# design.net
KiCad netlist of a schematic drawn in Altium Designer
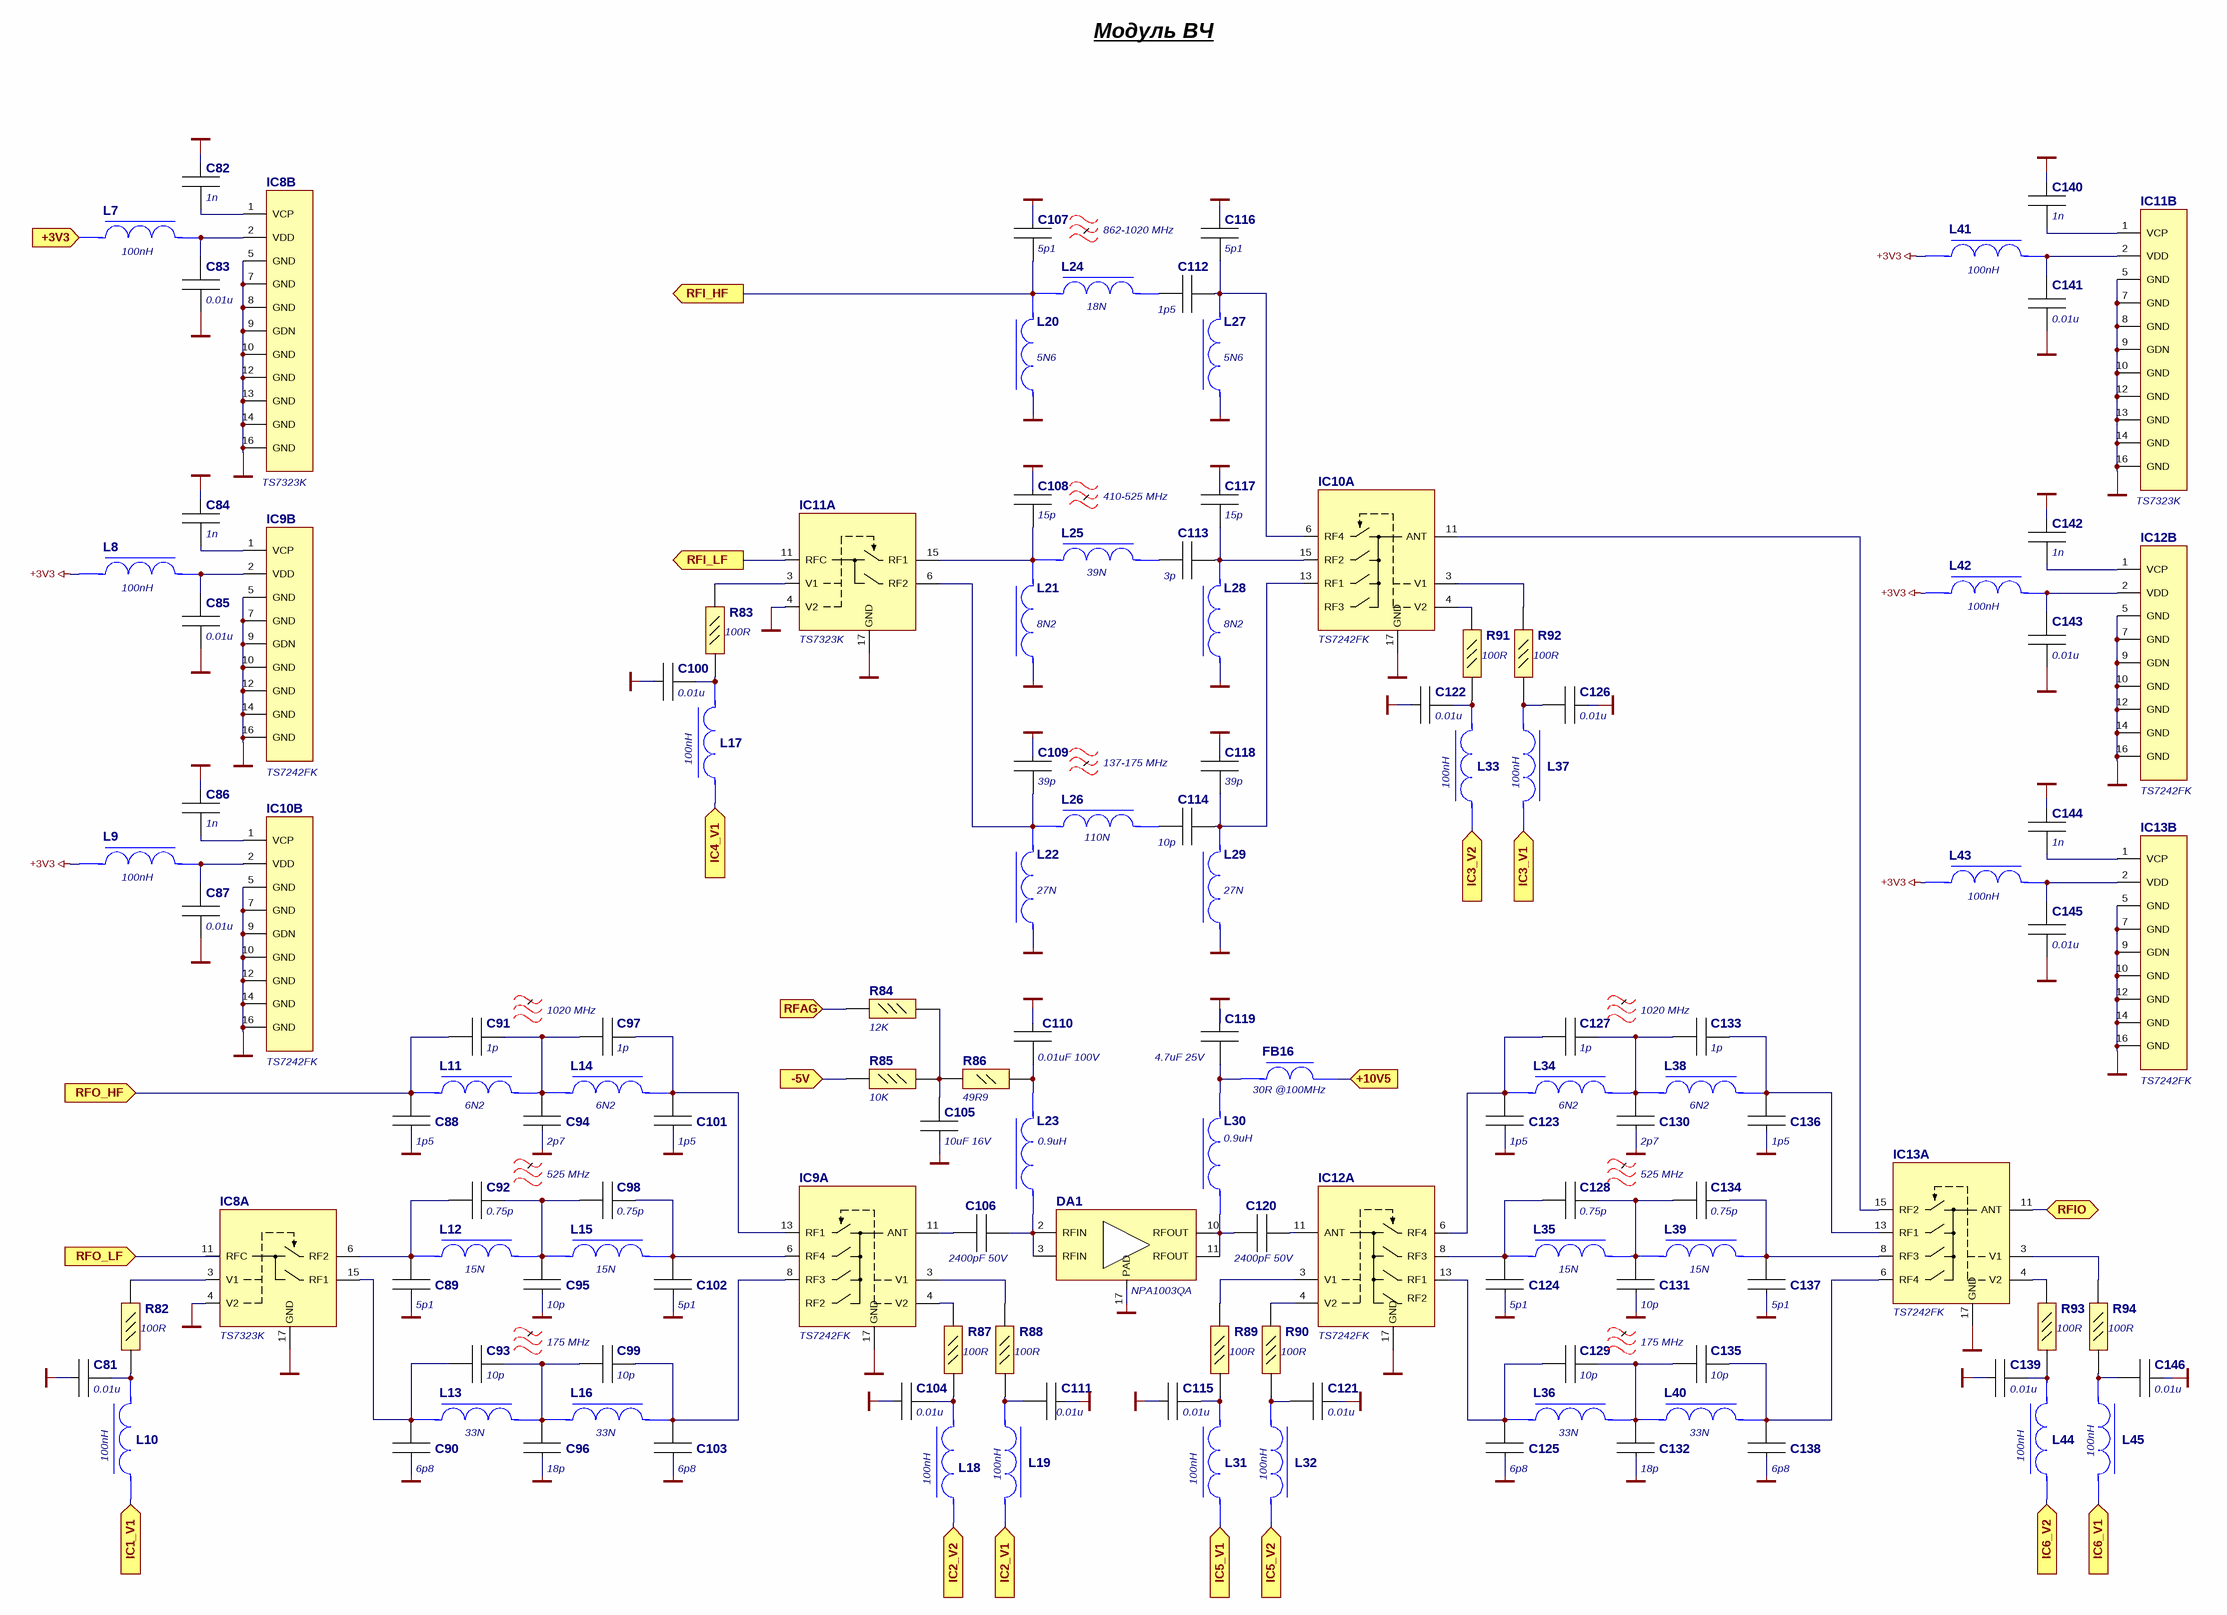
[diagram p0: Модуль ВЧ.SchDoc]

(export (version "E")
  (design (tool "Eeschema 10.0.6"))
  (components
    (comp (ref "C81")
      (value "0.01u")
      (footprint ":CAP0402 100x50x50")
      (description "±5% 35V Ceramic Capacitor C0G, NP0 0402 (1005 Metric)")
      (fields (field (name "MANUFACTURER_PART_NUMBER") "GRM1555CYA103JE01D"))
      (libsource (lib "Capacitors 0402") (part "GRM1555CYA103JE01D"))
    )
    (comp (ref "C82")
      (value "1n")
      (footprint ":CAP0402 100x50x50")
      (description "±5% 50V Ceramic Capacitor C0G, NP0 0402 (1005 Metric)")
      (fields (field (name "MANUFACTURER_PART_NUMBER") "GRM1555C1H102JA01J"))
      (libsource (lib "Capacitors 0402") (part "GRM1555C1H102JA01J"))
    )
    (comp (ref "C83")
      (value "0.01u")
      (footprint ":CAP0402 100x50x50")
      (description "±5% 35V Ceramic Capacitor C0G, NP0 0402 (1005 Metric)")
      (fields (field (name "MANUFACTURER_PART_NUMBER") "GRM1555CYA103JE01D"))
      (libsource (lib "Capacitors 0402") (part "GRM1555CYA103JE01D"))
    )
    (comp (ref "C84")
      (value "1n")
      (footprint ":CAP0402 100x50x50")
      (description "±5% 50V Ceramic Capacitor C0G, NP0 0402 (1005 Metric)")
      (fields (field (name "MANUFACTURER_PART_NUMBER") "GRM1555C1H102JA01J"))
      (libsource (lib "Capacitors 0402") (part "GRM1555C1H102JA01J"))
    )
    (comp (ref "C85")
      (value "0.01u")
      (footprint ":CAP0402 100x50x50")
      (description "±5% 35V Ceramic Capacitor C0G, NP0 0402 (1005 Metric)")
      (fields (field (name "MANUFACTURER_PART_NUMBER") "GRM1555CYA103JE01D"))
      (libsource (lib "Capacitors 0402") (part "GRM1555CYA103JE01D"))
    )
    (comp (ref "C86")
      (value "1n")
      (footprint ":CAP0402 100x50x50")
      (description "±5% 50V Ceramic Capacitor C0G, NP0 0402 (1005 Metric)")
      (fields (field (name "MANUFACTURER_PART_NUMBER") "GRM1555C1H102JA01J"))
      (libsource (lib "Capacitors 0402") (part "GRM1555C1H102JA01J"))
    )
    (comp (ref "C87")
      (value "0.01u")
      (footprint ":CAP0402 100x50x50")
      (description "±5% 35V Ceramic Capacitor C0G, NP0 0402 (1005 Metric)")
      (fields (field (name "MANUFACTURER_PART_NUMBER") "GRM1555CYA103JE01D"))
      (libsource (lib "Capacitors 0402") (part "GRM1555CYA103JE01D"))
    )
    (comp (ref "C88")
      (value "1p5")
      (footprint ":CAP0603 C1608х08")
      (description "Ceramic Capacitor ±0.1pF 250V C0G, NP0 0603 (1608 Metric)")
      (fields (field (name "MANUFACTURER_PART_NUMBER") "GQM1875C2E1R5BB12D"))
      (libsource (lib "Capacitors 0603 ±0.1pF 250V NP0") (part "GQM1875C2E1R5BB12D"))
    )
    (comp (ref "C89")
      (value "5p1")
      (footprint ":CAP0603 C1608х08")
      (description "Ceramic Capacitor ±0.1pF 250V C0G, NP0 0603 (1608 Metric)")
      (fields (field (name "MANUFACTURER_PART_NUMBER") "GQM1875C2E5R1BB12D"))
      (libsource (lib "Capacitors 0603 ±0.1pF 250V NP0") (part "GQM1875C2E5R1BB12D"))
    )
    (comp (ref "C90")
      (value "6p8")
      (footprint ":CAP0603 C1608х08")
      (description "Ceramic Capacitor ±0.1pF 250V C0G, NP0 0603 (1608 Metric)")
      (fields (field (name "MANUFACTURER_PART_NUMBER") "GQM1875C2E6R8BB12D"))
      (libsource (lib "Capacitors 0603 ±0.1pF 250V NP0") (part "GQM1875C2E6R8BB12D"))
    )
    (comp (ref "C91")
      (value "1p")
      (footprint ":CAP0603 C1608х08")
      (description "Ceramic Capacitor ±0.1pF 250V C0G, NP0 0603 (1608 Metric)")
      (fields (field (name "MANUFACTURER_PART_NUMBER") "GQM1875C2E1R0BB12D"))
      (libsource (lib "Capacitors 0603 ±0.1pF 250V NP0") (part "GQM1875C2E1R0BB12D"))
    )
    (comp (ref "C92")
      (value "0.75p")
      (footprint ":CAP0603 C1608х08")
      (description "Ceramic Capacitor ±0.1pF 250V C0G, NP0 0603 (1608 Metric)")
      (fields (field (name "MANUFACTURER_PART_NUMBER") "GQM1875C2ER75BB12D"))
      (libsource (lib "Capacitors 0603 ±0.1pF 250V NP0") (part "GQM1875C2ER75BB12D"))
    )
    (comp (ref "C93")
      (value "10p")
      (footprint ":CAP0603 C1608х08")
      (description "Ceramic Capacitor ±1% 250V C0G, NP0 0603 (1608 Metric)")
      (fields (field (name "MANUFACTURER_PART_NUMBER") "GQM1875C2E100FB12D"))
      (libsource (lib "Capacitors 0603 1% 250V NP0") (part "GQM1875C2E100FB12D"))
    )
    (comp (ref "C94")
      (value "2p7")
      (footprint ":CAP0603 C1608х08")
      (description "Ceramic Capacitor ±0.1pF 250V C0G, NP0 0603 (1608 Metric)")
      (fields (field (name "MANUFACTURER_PART_NUMBER") "GQM1875C2E2R7BB12D"))
      (libsource (lib "Capacitors 0603 ±0.1pF 250V NP0") (part "GQM1875C2E2R7BB12D"))
    )
    (comp (ref "C95")
      (value "10p")
      (footprint ":CAP0603 C1608х08")
      (description "Ceramic Capacitor ±1% 250V C0G, NP0 0603 (1608 Metric)")
      (fields (field (name "MANUFACTURER_PART_NUMBER") "GQM1875C2E100FB12D"))
      (libsource (lib "Capacitors 0603 1% 250V NP0") (part "GQM1875C2E100FB12D"))
    )
    (comp (ref "C96")
      (value "18p")
      (footprint ":CAP0603 C1608х08")
      (description "Ceramic Capacitor ±1% 250V C0G, NP0 0603 (1608 Metric)")
      (fields (field (name "MANUFACTURER_PART_NUMBER") "GQM1875C2E180FB12D"))
      (libsource (lib "Capacitors 0603 1% 250V NP0") (part "GQM1875C2E180FB12D"))
    )
    (comp (ref "C97")
      (value "1p")
      (footprint ":CAP0603 C1608х08")
      (description "Ceramic Capacitor ±0.1pF 250V C0G, NP0 0603 (1608 Metric)")
      (fields (field (name "MANUFACTURER_PART_NUMBER") "GQM1875C2E1R0BB12D"))
      (libsource (lib "Capacitors 0603 ±0.1pF 250V NP0") (part "GQM1875C2E1R0BB12D"))
    )
    (comp (ref "C98")
      (value "0.75p")
      (footprint ":CAP0603 C1608х08")
      (description "Ceramic Capacitor ±0.1pF 250V C0G, NP0 0603 (1608 Metric)")
      (fields (field (name "MANUFACTURER_PART_NUMBER") "GQM1875C2ER75BB12D"))
      (libsource (lib "Capacitors 0603 ±0.1pF 250V NP0") (part "GQM1875C2ER75BB12D"))
    )
    (comp (ref "C99")
      (value "10p")
      (footprint ":CAP0603 C1608х08")
      (description "Ceramic Capacitor ±1% 250V C0G, NP0 0603 (1608 Metric)")
      (fields (field (name "MANUFACTURER_PART_NUMBER") "GQM1875C2E100FB12D"))
      (libsource (lib "Capacitors 0603 1% 250V NP0") (part "GQM1875C2E100FB12D"))
    )
    (comp (ref "C100")
      (value "0.01u")
      (footprint ":CAP0402 100x50x50")
      (description "±5% 35V Ceramic Capacitor C0G, NP0 0402 (1005 Metric)")
      (fields (field (name "MANUFACTURER_PART_NUMBER") "GRM1555CYA103JE01D"))
      (libsource (lib "Capacitors 0402") (part "GRM1555CYA103JE01D"))
    )
    (comp (ref "C101")
      (value "1p5")
      (footprint ":CAP0603 C1608х08")
      (description "Ceramic Capacitor ±0.1pF 250V C0G, NP0 0603 (1608 Metric)")
      (fields (field (name "MANUFACTURER_PART_NUMBER") "GQM1875C2E1R5BB12D"))
      (libsource (lib "Capacitors 0603 ±0.1pF 250V NP0") (part "GQM1875C2E1R5BB12D"))
    )
    (comp (ref "C102")
      (value "5p1")
      (footprint ":CAP0603 C1608х08")
      (description "Ceramic Capacitor ±0.1pF 250V C0G, NP0 0603 (1608 Metric)")
      (fields (field (name "MANUFACTURER_PART_NUMBER") "GQM1875C2E5R1BB12D"))
      (libsource (lib "Capacitors 0603 ±0.1pF 250V NP0") (part "GQM1875C2E5R1BB12D"))
    )
    (comp (ref "C103")
      (value "6p8")
      (footprint ":CAP0603 C1608х08")
      (description "Ceramic Capacitor ±0.1pF 250V C0G, NP0 0603 (1608 Metric)")
      (fields (field (name "MANUFACTURER_PART_NUMBER") "GQM1875C2E6R8BB12D"))
      (libsource (lib "Capacitors 0603 ±0.1pF 250V NP0") (part "GQM1875C2E6R8BB12D"))
    )
    (comp (ref "C104")
      (value "0.01u")
      (footprint ":CAP0402 100x50x50")
      (description "±5% 35V Ceramic Capacitor C0G, NP0 0402 (1005 Metric)")
      (fields (field (name "MANUFACTURER_PART_NUMBER") "GRM1555CYA103JE01D"))
      (libsource (lib "Capacitors 0402") (part "GRM1555CYA103JE01D"))
    )
    (comp (ref "C105")
      (value "10uF 16V")
      (footprint ":CAP0805 C2012X125")
      (description "CAP CER 10uF 16V X5R 0805")
      (fields
        (field (name "MANUFACTURER_PART_NUMBER") "C2012X5R1C106M085AC")
        (field (name "MOUSER PART NUMBER") "810-C2012X5R1C106M-2")
      )
      (libsource (lib "Capacitors 0805") (part "C2012X5R1C106M085AC"))
    )
    (comp (ref "C106")
      (value "2400pF 50V")
      (footprint ":CAP0805 C2012X125")
      (description "2400pF 50V Ceramic Capacitor 0805 (2012 Metric)")
      (fields (field (name "MANUFACTURER_PART_NUMBER") "C08BL242X-5UN-X0T"))
      (libsource (lib "Capacitors 0805") (part "C08BL242X-5UN-X0T"))
    )
    (comp (ref "C107")
      (value "5p1")
      (footprint ":CAP0603 C1608х08")
      (description "Ceramic Capacitor ±0.1pF 250V C0G, NP0 0603 (1608 Metric)")
      (fields (field (name "MANUFACTURER_PART_NUMBER") "GQM1875C2E5R1BB12D"))
      (libsource (lib "Capacitors 0603 ±0.1pF 250V NP0") (part "GQM1875C2E5R1BB12D"))
    )
    (comp (ref "C108")
      (value "15p")
      (footprint ":CAP0603 C1608х08")
      (description "Ceramic Capacitor ±1% 250V C0G, NP0 0603 (1608 Metric)")
      (fields (field (name "MANUFACTURER_PART_NUMBER") "GQM1875C2E150FB12D"))
      (libsource (lib "Capacitors 0603 1% 250V NP0") (part "GQM1875C2E150FB12D"))
    )
    (comp (ref "C109")
      (value "39p")
      (footprint ":CAP0603 C1608х08")
      (description "Ceramic Capacitor ±1% 250V C0G, NP0 0603 (1608 Metric)")
      (fields (field (name "MANUFACTURER_PART_NUMBER") "GQM1875C2E390FB12D"))
      (libsource (lib "Capacitors 0603 1% 250V NP0") (part "GQM1875C2E390FB12D"))
    )
    (comp (ref "C110")
      (value "0.01uF 100V")
      (footprint ":CAP0603 C1608х08")
      (description "CAP CER 0.01uF 100V X7R 0603")
      (fields
        (field (name "MANUFACTURER_PART_NUMBER") "06031C103JAT2A")
        (field (name "MOUSER PART NUMBER") "581-06031C103J")
      )
      (libsource (lib "Capacitors 0603") (part "06031C103JAT2A"))
    )
    (comp (ref "C111")
      (value "0.01u")
      (footprint ":CAP0402 100x50x50")
      (description "±5% 35V Ceramic Capacitor C0G, NP0 0402 (1005 Metric)")
      (fields (field (name "MANUFACTURER_PART_NUMBER") "GRM1555CYA103JE01D"))
      (libsource (lib "Capacitors 0402") (part "GRM1555CYA103JE01D"))
    )
    (comp (ref "C112")
      (value "1p5")
      (footprint ":CAP0603 C1608х08")
      (description "Ceramic Capacitor ±0.1pF 250V C0G, NP0 0603 (1608 Metric)")
      (fields (field (name "MANUFACTURER_PART_NUMBER") "GQM1875C2E1R5BB12D"))
      (libsource (lib "Capacitors 0603 ±0.1pF 250V NP0") (part "GQM1875C2E1R5BB12D"))
    )
    (comp (ref "C113")
      (value "3p")
      (footprint ":CAP0603 C1608х08")
      (description "Ceramic Capacitor ±0.1pF 250V C0G, NP0 0603 (1608 Metric)")
      (fields (field (name "MANUFACTURER_PART_NUMBER") "GQM1875C2E3R0BB12D"))
      (libsource (lib "Capacitors 0603 ±0.1pF 250V NP0") (part "GQM1875C2E3R0BB12D"))
    )
    (comp (ref "C114")
      (value "10p")
      (footprint ":CAP0603 C1608х08")
      (description "Ceramic Capacitor ±1% 250V C0G, NP0 0603 (1608 Metric)")
      (fields (field (name "MANUFACTURER_PART_NUMBER") "GQM1875C2E100FB12D"))
      (libsource (lib "Capacitors 0603 1% 250V NP0") (part "GQM1875C2E100FB12D"))
    )
    (comp (ref "C115")
      (value "0.01u")
      (footprint ":CAP0402 100x50x50")
      (description "±5% 35V Ceramic Capacitor C0G, NP0 0402 (1005 Metric)")
      (fields (field (name "MANUFACTURER_PART_NUMBER") "GRM1555CYA103JE01D"))
      (libsource (lib "Capacitors 0402") (part "GRM1555CYA103JE01D"))
    )
    (comp (ref "C116")
      (value "5p1")
      (footprint ":CAP0603 C1608х08")
      (description "Ceramic Capacitor ±0.1pF 250V C0G, NP0 0603 (1608 Metric)")
      (fields (field (name "MANUFACTURER_PART_NUMBER") "GQM1875C2E5R1BB12D"))
      (libsource (lib "Capacitors 0603 ±0.1pF 250V NP0") (part "GQM1875C2E5R1BB12D"))
    )
    (comp (ref "C117")
      (value "15p")
      (footprint ":CAP0603 C1608х08")
      (description "Ceramic Capacitor ±1% 250V C0G, NP0 0603 (1608 Metric)")
      (fields (field (name "MANUFACTURER_PART_NUMBER") "GQM1875C2E150FB12D"))
      (libsource (lib "Capacitors 0603 1% 250V NP0") (part "GQM1875C2E150FB12D"))
    )
    (comp (ref "C118")
      (value "39p")
      (footprint ":CAP0603 C1608х08")
      (description "Ceramic Capacitor ±1% 250V C0G, NP0 0603 (1608 Metric)")
      (fields (field (name "MANUFACTURER_PART_NUMBER") "GQM1875C2E390FB12D"))
      (libsource (lib "Capacitors 0603 1% 250V NP0") (part "GQM1875C2E390FB12D"))
    )
    (comp (ref "C119")
      (value "4.7uF 25V")
      (footprint ":CAP0805 C2012X125")
      (description "CAP CER 4.7uF 25V X7R 0805")
      (fields (field (name "MANUFACTURER_PART_NUMBER") "GRM21BZ71E475KE15L"))
      (libsource (lib "Capacitors 0805") (part "GRM21BZ71E475KE15L"))
    )
    (comp (ref "C120")
      (value "2400pF 50V")
      (footprint ":CAP0805 C2012X125")
      (description "2400pF 50V Ceramic Capacitor 0805 (2012 Metric)")
      (fields (field (name "MANUFACTURER_PART_NUMBER") "C08BL242X-5UN-X0T"))
      (libsource (lib "Capacitors 0805") (part "C08BL242X-5UN-X0T"))
    )
    (comp (ref "C121")
      (value "0.01u")
      (footprint ":CAP0402 100x50x50")
      (description "±5% 35V Ceramic Capacitor C0G, NP0 0402 (1005 Metric)")
      (fields (field (name "MANUFACTURER_PART_NUMBER") "GRM1555CYA103JE01D"))
      (libsource (lib "Capacitors 0402") (part "GRM1555CYA103JE01D"))
    )
    (comp (ref "C122")
      (value "0.01u")
      (footprint ":CAP0402 100x50x50")
      (description "±5% 35V Ceramic Capacitor C0G, NP0 0402 (1005 Metric)")
      (fields (field (name "MANUFACTURER_PART_NUMBER") "GRM1555CYA103JE01D"))
      (libsource (lib "Capacitors 0402") (part "GRM1555CYA103JE01D"))
    )
    (comp (ref "C123")
      (value "1p5")
      (footprint ":CAP0603 C1608х08")
      (description "Ceramic Capacitor ±0.1pF 250V C0G, NP0 0603 (1608 Metric)")
      (fields (field (name "MANUFACTURER_PART_NUMBER") "GQM1875C2E1R5BB12D"))
      (libsource (lib "Capacitors 0603 ±0.1pF 250V NP0") (part "GQM1875C2E1R5BB12D"))
    )
    (comp (ref "C124")
      (value "5p1")
      (footprint ":CAP0603 C1608х08")
      (description "Ceramic Capacitor ±0.1pF 250V C0G, NP0 0603 (1608 Metric)")
      (fields (field (name "MANUFACTURER_PART_NUMBER") "GQM1875C2E5R1BB12D"))
      (libsource (lib "Capacitors 0603 ±0.1pF 250V NP0") (part "GQM1875C2E5R1BB12D"))
    )
    (comp (ref "C125")
      (value "6p8")
      (footprint ":CAP0603 C1608х08")
      (description "Ceramic Capacitor ±0.1pF 250V C0G, NP0 0603 (1608 Metric)")
      (fields (field (name "MANUFACTURER_PART_NUMBER") "GQM1875C2E6R8BB12D"))
      (libsource (lib "Capacitors 0603 ±0.1pF 250V NP0") (part "GQM1875C2E6R8BB12D"))
    )
    (comp (ref "C126")
      (value "0.01u")
      (footprint ":CAP0402 100x50x50")
      (description "±5% 35V Ceramic Capacitor C0G, NP0 0402 (1005 Metric)")
      (fields (field (name "MANUFACTURER_PART_NUMBER") "GRM1555CYA103JE01D"))
      (libsource (lib "Capacitors 0402") (part "GRM1555CYA103JE01D"))
    )
    (comp (ref "C127")
      (value "1p")
      (footprint ":CAP0603 C1608х08")
      (description "Ceramic Capacitor ±0.1pF 250V C0G, NP0 0603 (1608 Metric)")
      (fields (field (name "MANUFACTURER_PART_NUMBER") "GQM1875C2E1R0BB12D"))
      (libsource (lib "Capacitors 0603 ±0.1pF 250V NP0") (part "GQM1875C2E1R0BB12D"))
    )
    (comp (ref "C128")
      (value "0.75p")
      (footprint ":CAP0603 C1608х08")
      (description "Ceramic Capacitor ±0.1pF 250V C0G, NP0 0603 (1608 Metric)")
      (fields (field (name "MANUFACTURER_PART_NUMBER") "GQM1875C2ER75BB12D"))
      (libsource (lib "Capacitors 0603 ±0.1pF 250V NP0") (part "GQM1875C2ER75BB12D"))
    )
    (comp (ref "C129")
      (value "10p")
      (footprint ":CAP0603 C1608х08")
      (description "Ceramic Capacitor ±1% 250V C0G, NP0 0603 (1608 Metric)")
      (fields (field (name "MANUFACTURER_PART_NUMBER") "GQM1875C2E100FB12D"))
      (libsource (lib "Capacitors 0603 1% 250V NP0") (part "GQM1875C2E100FB12D"))
    )
    (comp (ref "C130")
      (value "2p7")
      (footprint ":CAP0603 C1608х08")
      (description "Ceramic Capacitor ±0.1pF 250V C0G, NP0 0603 (1608 Metric)")
      (fields (field (name "MANUFACTURER_PART_NUMBER") "GQM1875C2E2R7BB12D"))
      (libsource (lib "Capacitors 0603 ±0.1pF 250V NP0") (part "GQM1875C2E2R7BB12D"))
    )
    (comp (ref "C131")
      (value "10p")
      (footprint ":CAP0603 C1608х08")
      (description "Ceramic Capacitor ±1% 250V C0G, NP0 0603 (1608 Metric)")
      (fields (field (name "MANUFACTURER_PART_NUMBER") "GQM1875C2E100FB12D"))
      (libsource (lib "Capacitors 0603 1% 250V NP0") (part "GQM1875C2E100FB12D"))
    )
    (comp (ref "C132")
      (value "18p")
      (footprint ":CAP0603 C1608х08")
      (description "Ceramic Capacitor ±1% 250V C0G, NP0 0603 (1608 Metric)")
      (fields (field (name "MANUFACTURER_PART_NUMBER") "GQM1875C2E180FB12D"))
      (libsource (lib "Capacitors 0603 1% 250V NP0") (part "GQM1875C2E180FB12D"))
    )
    (comp (ref "C133")
      (value "1p")
      (footprint ":CAP0603 C1608х08")
      (description "Ceramic Capacitor ±0.1pF 250V C0G, NP0 0603 (1608 Metric)")
      (fields (field (name "MANUFACTURER_PART_NUMBER") "GQM1875C2E1R0BB12D"))
      (libsource (lib "Capacitors 0603 ±0.1pF 250V NP0") (part "GQM1875C2E1R0BB12D"))
    )
    (comp (ref "C134")
      (value "0.75p")
      (footprint ":CAP0603 C1608х08")
      (description "Ceramic Capacitor ±0.1pF 250V C0G, NP0 0603 (1608 Metric)")
      (fields (field (name "MANUFACTURER_PART_NUMBER") "GQM1875C2ER75BB12D"))
      (libsource (lib "Capacitors 0603 ±0.1pF 250V NP0") (part "GQM1875C2ER75BB12D"))
    )
    (comp (ref "C135")
      (value "10p")
      (footprint ":CAP0603 C1608х08")
      (description "Ceramic Capacitor ±1% 250V C0G, NP0 0603 (1608 Metric)")
      (fields (field (name "MANUFACTURER_PART_NUMBER") "GQM1875C2E100FB12D"))
      (libsource (lib "Capacitors 0603 1% 250V NP0") (part "GQM1875C2E100FB12D"))
    )
    (comp (ref "C136")
      (value "1p5")
      (footprint ":CAP0603 C1608х08")
      (description "Ceramic Capacitor ±0.1pF 250V C0G, NP0 0603 (1608 Metric)")
      (fields (field (name "MANUFACTURER_PART_NUMBER") "GQM1875C2E1R5BB12D"))
      (libsource (lib "Capacitors 0603 ±0.1pF 250V NP0") (part "GQM1875C2E1R5BB12D"))
    )
    (comp (ref "C137")
      (value "5p1")
      (footprint ":CAP0603 C1608х08")
      (description "Ceramic Capacitor ±0.1pF 250V C0G, NP0 0603 (1608 Metric)")
      (fields (field (name "MANUFACTURER_PART_NUMBER") "GQM1875C2E5R1BB12D"))
      (libsource (lib "Capacitors 0603 ±0.1pF 250V NP0") (part "GQM1875C2E5R1BB12D"))
    )
    (comp (ref "C138")
      (value "6p8")
      (footprint ":CAP0603 C1608х08")
      (description "Ceramic Capacitor ±0.1pF 250V C0G, NP0 0603 (1608 Metric)")
      (fields (field (name "MANUFACTURER_PART_NUMBER") "GQM1875C2E6R8BB12D"))
      (libsource (lib "Capacitors 0603 ±0.1pF 250V NP0") (part "GQM1875C2E6R8BB12D"))
    )
    (comp (ref "C139")
      (value "0.01u")
      (footprint ":CAP0402 100x50x50")
      (description "±5% 35V Ceramic Capacitor C0G, NP0 0402 (1005 Metric)")
      (fields (field (name "MANUFACTURER_PART_NUMBER") "GRM1555CYA103JE01D"))
      (libsource (lib "Capacitors 0402") (part "GRM1555CYA103JE01D"))
    )
    (comp (ref "C140")
      (value "1n")
      (footprint ":CAP0402 100x50x50")
      (description "±5% 50V Ceramic Capacitor C0G, NP0 0402 (1005 Metric)")
      (fields (field (name "MANUFACTURER_PART_NUMBER") "GRM1555C1H102JA01J"))
      (libsource (lib "Capacitors 0402") (part "GRM1555C1H102JA01J"))
    )
    (comp (ref "C141")
      (value "0.01u")
      (footprint ":CAP0402 100x50x50")
      (description "±5% 35V Ceramic Capacitor C0G, NP0 0402 (1005 Metric)")
      (fields (field (name "MANUFACTURER_PART_NUMBER") "GRM1555CYA103JE01D"))
      (libsource (lib "Capacitors 0402") (part "GRM1555CYA103JE01D"))
    )
    (comp (ref "C142")
      (value "1n")
      (footprint ":CAP0402 100x50x50")
      (description "±5% 50V Ceramic Capacitor C0G, NP0 0402 (1005 Metric)")
      (fields (field (name "MANUFACTURER_PART_NUMBER") "GRM1555C1H102JA01J"))
      (libsource (lib "Capacitors 0402") (part "GRM1555C1H102JA01J"))
    )
    (comp (ref "C143")
      (value "0.01u")
      (footprint ":CAP0402 100x50x50")
      (description "±5% 35V Ceramic Capacitor C0G, NP0 0402 (1005 Metric)")
      (fields (field (name "MANUFACTURER_PART_NUMBER") "GRM1555CYA103JE01D"))
      (libsource (lib "Capacitors 0402") (part "GRM1555CYA103JE01D"))
    )
    (comp (ref "C144")
      (value "1n")
      (footprint ":CAP0402 100x50x50")
      (description "±5% 50V Ceramic Capacitor C0G, NP0 0402 (1005 Metric)")
      (fields (field (name "MANUFACTURER_PART_NUMBER") "GRM1555C1H102JA01J"))
      (libsource (lib "Capacitors 0402") (part "GRM1555C1H102JA01J"))
    )
    (comp (ref "C145")
      (value "0.01u")
      (footprint ":CAP0402 100x50x50")
      (description "±5% 35V Ceramic Capacitor C0G, NP0 0402 (1005 Metric)")
      (fields (field (name "MANUFACTURER_PART_NUMBER") "GRM1555CYA103JE01D"))
      (libsource (lib "Capacitors 0402") (part "GRM1555CYA103JE01D"))
    )
    (comp (ref "C146")
      (value "0.01u")
      (footprint ":CAP0402 100x50x50")
      (description "±5% 35V Ceramic Capacitor C0G, NP0 0402 (1005 Metric)")
      (fields (field (name "MANUFACTURER_PART_NUMBER") "GRM1555CYA103JE01D"))
      (libsource (lib "Capacitors 0402") (part "GRM1555CYA103JE01D"))
    )
    (comp (ref "DA1")
      (value "NPA1003QA")
      (footprint ":QFN16 P400X400X95-17N-D")
      (description "GaN 20 - 1500 MHz Power Amplifier 16dB 5W")
      (fields (field (name "MOUSER PART NUMBER") "937-NPA1003QA"))
      (libsource (lib "Analog ICs") (part "NPA1003QA"))
    )
    (comp (ref "FB16")
      (value "30R @100MHz")
      (footprint ":FER BLM18SP300SN1D")
      (description "30 Ohms @ 100MHz 1 Power Line Ferrite Bead 0603 (1608 Metric) 6A 8mOhm")
      (fields
        (field (name "MANUFACTURER_PART_NUMBER") "BLM18SP300SN1D")
        (field (name "MOUSER PART NUMBER") "81-BLM18SP300SN1D")
      )
      (libsource (lib "Ferrite Bead") (part "BLM18SP300SN1D"))
    )
    (comp (ref "IC8")
      (value "TS7323K")
      (footprint ":QFN16 P300X300X80-17N-D")
      (description "SPDT Switch 1MHz to 1GHz")
      (fields (field (name "MANUFACTURER_PART_NUMBER") "TS7323KMTRPBF"))
      (libsource (lib "") (part "TS7323K_1"))
    )
    (comp (ref "IC9")
      (value "TS7242FK")
      (footprint ":QFN16 P300X300X80-17N-D")
      (description "SP4T Switch 10MHz to 3GHz")
      (fields (field (name "MANUFACTURER_PART_NUMBER") "TS7242FKMTRPBF"))
      (libsource (lib "Switching and Relays") (part "TS7242FK"))
    )
    (comp (ref "IC10")
      (value "TS7242FK")
      (footprint ":QFN16 P300X300X80-17N-D")
      (description "SP4T Switch 10MHz to 3GHz")
      (fields (field (name "MANUFACTURER_PART_NUMBER") "TS7242FKMTRPBF"))
      (libsource (lib "Switching and Relays") (part "TS7242FK"))
    )
    (comp (ref "IC11")
      (value "TS7323K")
      (footprint ":QFN16 P300X300X80-17N-D")
      (description "SPDT Switch 1MHz to 1GHz")
      (fields (field (name "MANUFACTURER_PART_NUMBER") "TS7323KMTRPBF"))
      (libsource (lib "Switching and Relays") (part "TS7323K"))
    )
    (comp (ref "IC12")
      (value "TS7242FK")
      (footprint ":QFN16 P300X300X80-17N-D")
      (description "SP4T Switch 10MHz to 3GHz")
      (fields (field (name "MANUFACTURER_PART_NUMBER") "TS7242FKMTRPBF"))
      (libsource (lib "Switching and Relays") (part "TS7242FK"))
    )
    (comp (ref "IC13")
      (value "TS7242FK")
      (footprint ":QFN16 P300X300X80-17N-D")
      (description "SP4T Switch 10MHz to 3GHz")
      (fields (field (name "MANUFACTURER_PART_NUMBER") "TS7242FKMTRPBF"))
      (libsource (lib "") (part "TS7242FK_2"))
    )
    (comp (ref "L7")
      (value "100nH")
      (footprint ":IND 0402")
      (description "Unshielded Multilayer Inductor 0402 5%")
      (fields (field (name "MANUFACTURER_PART_NUMBER") "LQG15HNR10J02D"))
      (libsource (lib "Inductance 0402") (part "LQG15HNR10J02D"))
    )
    (comp (ref "L8")
      (value "100nH")
      (footprint ":IND 0402")
      (description "Unshielded Multilayer Inductor 0402 5%")
      (fields (field (name "MANUFACTURER_PART_NUMBER") "LQG15HNR10J02D"))
      (libsource (lib "Inductance 0402") (part "LQG15HNR10J02D"))
    )
    (comp (ref "L9")
      (value "100nH")
      (footprint ":IND 0402")
      (description "Unshielded Multilayer Inductor 0402 5%")
      (fields (field (name "MANUFACTURER_PART_NUMBER") "LQG15HNR10J02D"))
      (libsource (lib "Inductance 0402") (part "LQG15HNR10J02D"))
    )
    (comp (ref "L10")
      (value "100nH")
      (footprint ":IND 0402")
      (description "Unshielded Multilayer Inductor 0402 5%")
      (fields (field (name "MANUFACTURER_PART_NUMBER") "LQG15HNR10J02D"))
      (libsource (lib "Inductance 0402") (part "LQG15HNR10J02D"))
    )
    (comp (ref "L11")
      (value "~")
      (footprint ":IND 0603 (1608)")
      (fields
        (field (name "MANUFACTURER_PART_NUMBER") "LQW18AN")
        (field (name "MANUFACTURER_PART_NUMBER (PART 2: VALUE)") "6N2")
      )
      (libsource (lib "Inductance 0603") (part "LQW18AN...G8ZD"))
    )
    (comp (ref "L12")
      (value "LQW18AN...G8ZD")
      (footprint ":IND 0603 (1608)")
      (fields
        (field (name "MANUFACTURER_PART_NUMBER") "LQW18AN")
        (field (name "MANUFACTURER_PART_NUMBER (PART 2: VALUE)") "15N")
      )
      (libsource (lib "Inductance 0603") (part "LQW18AN...G8ZD"))
    )
    (comp (ref "L13")
      (value "LQW18AN...G8ZD")
      (footprint ":IND 0603 (1608)")
      (fields
        (field (name "MANUFACTURER_PART_NUMBER") "LQW18AN")
        (field (name "MANUFACTURER_PART_NUMBER (PART 2: VALUE)") "33N")
      )
      (libsource (lib "Inductance 0603") (part "LQW18AN...G8ZD"))
    )
    (comp (ref "L14")
      (value "LQW18AN...G8ZD")
      (footprint ":IND 0603 (1608)")
      (fields
        (field (name "MANUFACTURER_PART_NUMBER") "LQW18AN")
        (field (name "MANUFACTURER_PART_NUMBER (PART 2: VALUE)") "6N2")
      )
      (libsource (lib "Inductance 0603") (part "LQW18AN...G8ZD"))
    )
    (comp (ref "L15")
      (value "LQW18AN...G8ZD")
      (footprint ":IND 0603 (1608)")
      (fields
        (field (name "MANUFACTURER_PART_NUMBER") "LQW18AN")
        (field (name "MANUFACTURER_PART_NUMBER (PART 2: VALUE)") "15N")
      )
      (libsource (lib "Inductance 0603") (part "LQW18AN...G8ZD"))
    )
    (comp (ref "L16")
      (value "LQW18AN...G8ZD")
      (footprint ":IND 0603 (1608)")
      (fields
        (field (name "MANUFACTURER_PART_NUMBER") "LQW18AN")
        (field (name "MANUFACTURER_PART_NUMBER (PART 2: VALUE)") "33N")
      )
      (libsource (lib "Inductance 0603") (part "LQW18AN...G8ZD"))
    )
    (comp (ref "L17")
      (value "100nH")
      (footprint ":IND 0402")
      (description "Unshielded Multilayer Inductor 0402 5%")
      (fields (field (name "MANUFACTURER_PART_NUMBER") "LQG15HNR10J02D"))
      (libsource (lib "Inductance 0402") (part "LQG15HNR10J02D"))
    )
    (comp (ref "L18")
      (value "100nH")
      (footprint ":IND 0402")
      (description "Unshielded Multilayer Inductor 0402 5%")
      (fields (field (name "MANUFACTURER_PART_NUMBER") "LQG15HNR10J02D"))
      (libsource (lib "Inductance 0402") (part "LQG15HNR10J02D"))
    )
    (comp (ref "L19")
      (value "100nH")
      (footprint ":IND 0402")
      (description "Unshielded Multilayer Inductor 0402 5%")
      (fields (field (name "MANUFACTURER_PART_NUMBER") "LQG15HNR10J02D"))
      (libsource (lib "") (part "LQG15HNR10J02D_1"))
    )
    (comp (ref "L20")
      (value "~")
      (footprint ":IND 0603 (1608)")
      (fields
        (field (name "MANUFACTURER_PART_NUMBER") "LQW18AN")
        (field (name "MANUFACTURER_PART_NUMBER (PART 2: VALUE)") "5N6")
      )
      (libsource (lib "Inductance 0603") (part "LQW18AN...G8ZD"))
    )
    (comp (ref "L21")
      (value "LQW18AN...G8ZD")
      (footprint ":IND 0603 (1608)")
      (fields
        (field (name "MANUFACTURER_PART_NUMBER") "LQW18AN")
        (field (name "MANUFACTURER_PART_NUMBER (PART 2: VALUE)") "8N2")
      )
      (libsource (lib "Inductance 0603") (part "LQW18AN...G8ZD"))
    )
    (comp (ref "L22")
      (value "LQW18AN...G8ZD")
      (footprint ":IND 0603 (1608)")
      (fields
        (field (name "MANUFACTURER_PART_NUMBER") "LQW18AN")
        (field (name "MANUFACTURER_PART_NUMBER (PART 2: VALUE)") "27N")
      )
      (libsource (lib "Inductance 0603") (part "LQW18AN...G8ZD"))
    )
    (comp (ref "L23")
      (value "0.9uH")
      (footprint ":IND 1008AF901XJLC")
      (fields (field (name "MANUFACTURER_PART_NUMBER") "1008AF-901XJLC"))
      (libsource (lib "Inductance") (part "1008AF-901XJLC"))
    )
    (comp (ref "L24")
      (value "LQW18AN...G8ZD")
      (footprint ":IND 0603 (1608)")
      (fields
        (field (name "MANUFACTURER_PART_NUMBER") "LQW18AN")
        (field (name "MANUFACTURER_PART_NUMBER (PART 2: VALUE)") "18N")
      )
      (libsource (lib "Inductance 0603") (part "LQW18AN...G8ZD"))
    )
    (comp (ref "L25")
      (value "LQW18AN...G8ZD")
      (footprint ":IND 0603 (1608)")
      (fields
        (field (name "MANUFACTURER_PART_NUMBER") "LQW18AN")
        (field (name "MANUFACTURER_PART_NUMBER (PART 2: VALUE)") "39N")
      )
      (libsource (lib "Inductance 0603") (part "LQW18AN...G8ZD"))
    )
    (comp (ref "L26")
      (value "110N")
      (footprint ":IND 0603 (1608)")
      (fields (field (name "MANUFACTURER_PART_NUMBER") "LQW18AN"))
      (libsource (lib "Inductance 0603") (part "LQW18AN...G8ZD"))
    )
    (comp (ref "L27")
      (value "LQW18AN...G8ZD")
      (footprint ":IND 0603 (1608)")
      (fields
        (field (name "MANUFACTURER_PART_NUMBER") "LQW18AN")
        (field (name "MANUFACTURER_PART_NUMBER (PART 2: VALUE)") "5N6")
      )
      (libsource (lib "Inductance 0603") (part "LQW18AN...G8ZD"))
    )
    (comp (ref "L28")
      (value "LQW18AN...G8ZD")
      (footprint ":IND 0603 (1608)")
      (fields
        (field (name "MANUFACTURER_PART_NUMBER") "LQW18AN")
        (field (name "MANUFACTURER_PART_NUMBER (PART 2: VALUE)") "8N2")
      )
      (libsource (lib "Inductance 0603") (part "LQW18AN...G8ZD"))
    )
    (comp (ref "L29")
      (value "LQW18AN...G8ZD")
      (footprint ":IND 0603 (1608)")
      (fields
        (field (name "MANUFACTURER_PART_NUMBER") "LQW18AN")
        (field (name "MANUFACTURER_PART_NUMBER (PART 2: VALUE)") "27N")
      )
      (libsource (lib "Inductance 0603") (part "LQW18AN...G8ZD"))
    )
    (comp (ref "L30")
      (value "0.9uH")
      (footprint ":IND 1008AF901XJLC")
      (fields (field (name "MANUFACTURER_PART_NUMBER") "1008AF-901XJLC"))
      (libsource (lib "Inductance") (part "1008AF-901XJLC"))
    )
    (comp (ref "L31")
      (value "100nH")
      (footprint ":IND 0402")
      (description "Unshielded Multilayer Inductor 0402 5%")
      (fields (field (name "MANUFACTURER_PART_NUMBER") "LQG15HNR10J02D"))
      (libsource (lib "Inductance 0402") (part "LQG15HNR10J02D"))
    )
    (comp (ref "L32")
      (value "100nH")
      (footprint ":IND 0402")
      (description "Unshielded Multilayer Inductor 0402 5%")
      (fields (field (name "MANUFACTURER_PART_NUMBER") "LQG15HNR10J02D"))
      (libsource (lib "") (part "LQG15HNR10J02D_1"))
    )
    (comp (ref "L33")
      (value "100nH")
      (footprint ":IND 0402")
      (description "Unshielded Multilayer Inductor 0402 5%")
      (fields (field (name "MANUFACTURER_PART_NUMBER") "LQG15HNR10J02D"))
      (libsource (lib "Inductance 0402") (part "LQG15HNR10J02D"))
    )
    (comp (ref "L34")
      (value "LQW18AN...G8ZD")
      (footprint ":IND 0603 (1608)")
      (fields
        (field (name "MANUFACTURER_PART_NUMBER") "LQW18AN")
        (field (name "MANUFACTURER_PART_NUMBER (PART 2: VALUE)") "6N2")
      )
      (libsource (lib "Inductance 0603") (part "LQW18AN...G8ZD"))
    )
    (comp (ref "L35")
      (value "LQW18AN...G8ZD")
      (footprint ":IND 0603 (1608)")
      (fields
        (field (name "MANUFACTURER_PART_NUMBER") "LQW18AN")
        (field (name "MANUFACTURER_PART_NUMBER (PART 2: VALUE)") "15N")
      )
      (libsource (lib "Inductance 0603") (part "LQW18AN...G8ZD"))
    )
    (comp (ref "L36")
      (value "LQW18AN...G8ZD")
      (footprint ":IND 0603 (1608)")
      (fields
        (field (name "MANUFACTURER_PART_NUMBER") "LQW18AN")
        (field (name "MANUFACTURER_PART_NUMBER (PART 2: VALUE)") "33N")
      )
      (libsource (lib "Inductance 0603") (part "LQW18AN...G8ZD"))
    )
    (comp (ref "L37")
      (value "100nH")
      (footprint ":IND 0402")
      (description "Unshielded Multilayer Inductor 0402 5%")
      (fields (field (name "MANUFACTURER_PART_NUMBER") "LQG15HNR10J02D"))
      (libsource (lib "") (part "LQG15HNR10J02D_1"))
    )
    (comp (ref "L38")
      (value "LQW18AN...G8ZD")
      (footprint ":IND 0603 (1608)")
      (fields
        (field (name "MANUFACTURER_PART_NUMBER") "LQW18AN")
        (field (name "MANUFACTURER_PART_NUMBER (PART 2: VALUE)") "6N2")
      )
      (libsource (lib "Inductance 0603") (part "LQW18AN...G8ZD"))
    )
    (comp (ref "L39")
      (value "LQW18AN...G8ZD")
      (footprint ":IND 0603 (1608)")
      (fields
        (field (name "MANUFACTURER_PART_NUMBER") "LQW18AN")
        (field (name "MANUFACTURER_PART_NUMBER (PART 2: VALUE)") "15N")
      )
      (libsource (lib "Inductance 0603") (part "LQW18AN...G8ZD"))
    )
    (comp (ref "L40")
      (value "LQW18AN...G8ZD")
      (footprint ":IND 0603 (1608)")
      (fields
        (field (name "MANUFACTURER_PART_NUMBER") "LQW18AN")
        (field (name "MANUFACTURER_PART_NUMBER (PART 2: VALUE)") "33N")
      )
      (libsource (lib "Inductance 0603") (part "LQW18AN...G8ZD"))
    )
    (comp (ref "L41")
      (value "100nH")
      (footprint ":IND 0402")
      (description "Unshielded Multilayer Inductor 0402 5%")
      (fields (field (name "MANUFACTURER_PART_NUMBER") "LQG15HNR10J02D"))
      (libsource (lib "Inductance 0402") (part "LQG15HNR10J02D"))
    )
    (comp (ref "L42")
      (value "100nH")
      (footprint ":IND 0402")
      (description "Unshielded Multilayer Inductor 0402 5%")
      (fields (field (name "MANUFACTURER_PART_NUMBER") "LQG15HNR10J02D"))
      (libsource (lib "Inductance 0402") (part "LQG15HNR10J02D"))
    )
    (comp (ref "L43")
      (value "100nH")
      (footprint ":IND 0402")
      (description "Unshielded Multilayer Inductor 0402 5%")
      (fields (field (name "MANUFACTURER_PART_NUMBER") "LQG15HNR10J02D"))
      (libsource (lib "Inductance 0402") (part "LQG15HNR10J02D"))
    )
    (comp (ref "L44")
      (value "100nH")
      (footprint ":IND 0402")
      (description "Unshielded Multilayer Inductor 0402 5%")
      (fields (field (name "MANUFACTURER_PART_NUMBER") "LQG15HNR10J02D"))
      (libsource (lib "Inductance 0402") (part "LQG15HNR10J02D"))
    )
    (comp (ref "L45")
      (value "100nH")
      (footprint ":IND 0402")
      (description "Unshielded Multilayer Inductor 0402 5%")
      (fields (field (name "MANUFACTURER_PART_NUMBER") "LQG15HNR10J02D"))
      (libsource (lib "") (part "LQG15HNR10J02D_1"))
    )
    (comp (ref "R82")
      (value "RC0402FR-07")
      (footprint ":RES0402")
      (fields (field (name "MANUFACTURER_PART_NUMBER (PART 2: VALUE)") "100R"))
      (libsource (lib "Resistors 0402") (part "RC0402FR-07"))
    )
    (comp (ref "R83")
      (value "RC0402FR-07")
      (footprint ":RES0402")
      (fields (field (name "MANUFACTURER_PART_NUMBER (PART 2: VALUE)") "100R"))
      (libsource (lib "Resistors 0402") (part "RC0402FR-07"))
    )
    (comp (ref "R84")
      (value "RC0402FR-07")
      (footprint ":RES0402")
      (fields (field (name "MANUFACTURER_PART_NUMBER (PART 2: VALUE)") "12K"))
      (libsource (lib "") (part "RC0402FR-07_1"))
    )
    (comp (ref "R85")
      (value "RC0402FR-07")
      (footprint ":RES0402")
      (fields (field (name "MANUFACTURER_PART_NUMBER (PART 2: VALUE)") "10K"))
      (libsource (lib "") (part "RC0402FR-07_1"))
    )
    (comp (ref "R86")
      (value "49R9")
      (footprint ":RES0805")
      (description "49.9 Ohms ±1% 0.125W, 1/8W Chip Resistor 0805 (2012 Metric) Automotive AEC-Q200 Thick Film")
      (fields
        (field (name "MANUFACTURER_PART_NUMBER") "ERJ-6ENF49R9V")
        (field (name "MOUSER PART NUMBER") "667-ERJ-6ENF49R9V")
      )
      (libsource (lib "Resistors 0805") (part "ERJ-6ENF49R9V"))
    )
    (comp (ref "R87")
      (value "RC0402FR-07")
      (footprint ":RES0402")
      (fields (field (name "MANUFACTURER_PART_NUMBER (PART 2: VALUE)") "100R"))
      (libsource (lib "Resistors 0402") (part "RC0402FR-07"))
    )
    (comp (ref "R88")
      (value "RC0402FR-07")
      (footprint ":RES0402")
      (fields (field (name "MANUFACTURER_PART_NUMBER (PART 2: VALUE)") "100R"))
      (libsource (lib "Resistors 0402") (part "RC0402FR-07"))
    )
    (comp (ref "R89")
      (value "RC0402FR-07")
      (footprint ":RES0402")
      (fields (field (name "MANUFACTURER_PART_NUMBER (PART 2: VALUE)") "100R"))
      (libsource (lib "Resistors 0402") (part "RC0402FR-07"))
    )
    (comp (ref "R90")
      (value "RC0402FR-07")
      (footprint ":RES0402")
      (fields (field (name "MANUFACTURER_PART_NUMBER (PART 2: VALUE)") "100R"))
      (libsource (lib "Resistors 0402") (part "RC0402FR-07"))
    )
    (comp (ref "R91")
      (value "RC0402FR-07")
      (footprint ":RES0402")
      (fields (field (name "MANUFACTURER_PART_NUMBER (PART 2: VALUE)") "100R"))
      (libsource (lib "Resistors 0402") (part "RC0402FR-07"))
    )
    (comp (ref "R92")
      (value "RC0402FR-07")
      (footprint ":RES0402")
      (fields (field (name "MANUFACTURER_PART_NUMBER (PART 2: VALUE)") "100R"))
      (libsource (lib "Resistors 0402") (part "RC0402FR-07"))
    )
    (comp (ref "R93")
      (value "RC0402FR-07")
      (footprint ":RES0402")
      (fields (field (name "MANUFACTURER_PART_NUMBER (PART 2: VALUE)") "100R"))
      (libsource (lib "Resistors 0402") (part "RC0402FR-07"))
    )
    (comp (ref "R94")
      (value "RC0402FR-07")
      (footprint ":RES0402")
      (fields (field (name "MANUFACTURER_PART_NUMBER (PART 2: VALUE)") "100R"))
      (libsource (lib "Resistors 0402") (part "RC0402FR-07"))
    )
  )
  (nets
    (net (code "1") (name "+3V3") (class "Default")
      (node (ref "L41") (pin "1") (pinfunction "1_1") (pintype "passive"))
      (node (ref "L42") (pin "1") (pinfunction "1_1") (pintype "passive"))
      (node (ref "L43") (pin "1") (pinfunction "1_1") (pintype "passive"))
      (node (ref "L7") (pin "1") (pinfunction "1_1") (pintype "passive"))
      (node (ref "L8") (pin "1") (pinfunction "1_1") (pintype "passive"))
      (node (ref "L9") (pin "1") (pinfunction "1_1") (pintype "passive"))
    )
    (net (code "2") (name "/+10V5") (class "Default")
      (node (ref "FB16") (pin "2") (pinfunction "2_2") (pintype "passive"))
    )
    (net (code "3") (name "/-5V") (class "Default")
      (node (ref "R85") (pin "2") (pinfunction "2_2") (pintype "passive"))
    )
    (net (code "4") (name "/IC1_V1") (class "Default")
      (node (ref "L10") (pin "1") (pinfunction "1_1") (pintype "passive"))
    )
    (net (code "5") (name "/IC2_V1") (class "Default")
      (node (ref "L19") (pin "1") (pinfunction "1_1") (pintype "passive"))
    )
    (net (code "6") (name "/IC2_V2") (class "Default")
      (node (ref "L18") (pin "1") (pinfunction "1_1") (pintype "passive"))
    )
    (net (code "7") (name "/IC3_V1") (class "Default")
      (node (ref "L37") (pin "1") (pinfunction "1_1") (pintype "passive"))
    )
    (net (code "8") (name "/IC3_V2") (class "Default")
      (node (ref "L33") (pin "1") (pinfunction "1_1") (pintype "passive"))
    )
    (net (code "9") (name "/IC4_V1") (class "Default")
      (node (ref "L17") (pin "1") (pinfunction "1_1") (pintype "passive"))
    )
    (net (code "10") (name "/IC5_V1") (class "Default")
      (node (ref "L31") (pin "1") (pinfunction "1_1") (pintype "passive"))
    )
    (net (code "11") (name "/IC5_V2") (class "Default")
      (node (ref "L32") (pin "1") (pinfunction "1_1") (pintype "passive"))
    )
    (net (code "12") (name "/IC6_V1") (class "Default")
      (node (ref "L45") (pin "1") (pinfunction "1_1") (pintype "passive"))
    )
    (net (code "13") (name "/IC6_V2") (class "Default")
      (node (ref "L44") (pin "1") (pinfunction "1_1") (pintype "passive"))
    )
    (net (code "14") (name "/RFAG") (class "Default")
      (node (ref "R84") (pin "2") (pinfunction "2_2") (pintype "passive"))
    )
    (net (code "15") (name "/RFIO") (class "Default")
      (node (ref "IC13") (pin "11") (pinfunction "ANT_11") (pintype "passive"))
    )
    (net (code "16") (name "/RFI_HF") (class "Default")
      (node (ref "C107") (pin "1") (pinfunction "1_1") (pintype "passive"))
      (node (ref "L20") (pin "2") (pinfunction "2_2") (pintype "passive"))
      (node (ref "L24") (pin "1") (pinfunction "1_1") (pintype "passive"))
    )
    (net (code "17") (name "/RFI_LF") (class "Default")
      (node (ref "IC11") (pin "11") (pinfunction "RFC_11") (pintype "passive"))
    )
    (net (code "18") (name "/RFO_HF") (class "Default")
      (node (ref "C88") (pin "1") (pinfunction "1_1") (pintype "passive"))
      (node (ref "C91") (pin "1") (pinfunction "1_1") (pintype "passive"))
      (node (ref "L11") (pin "1") (pinfunction "1_1") (pintype "passive"))
    )
    (net (code "19") (name "/RFO_LF") (class "Default")
      (node (ref "IC8") (pin "11") (pinfunction "RFC_11") (pintype "passive"))
    )
    (net (code "20") (name "GND") (class "Default")
      (node (ref "C100") (pin "2") (pinfunction "2_2") (pintype "passive"))
      (node (ref "C101") (pin "2") (pinfunction "2_2") (pintype "passive"))
      (node (ref "C102") (pin "2") (pinfunction "2_2") (pintype "passive"))
      (node (ref "C103") (pin "2") (pinfunction "2_2") (pintype "passive"))
      (node (ref "C104") (pin "2") (pinfunction "2_2") (pintype "passive"))
      (node (ref "C105") (pin "1") (pinfunction "1_1") (pintype "passive"))
      (node (ref "C107") (pin "2") (pinfunction "2_2") (pintype "passive"))
      (node (ref "C108") (pin "2") (pinfunction "2_2") (pintype "passive"))
      (node (ref "C109") (pin "2") (pinfunction "2_2") (pintype "passive"))
      (node (ref "C110") (pin "1") (pinfunction "1_1") (pintype "passive"))
      (node (ref "C111") (pin "2") (pinfunction "2_2") (pintype "passive"))
      (node (ref "C115") (pin "2") (pinfunction "2_2") (pintype "passive"))
      (node (ref "C116") (pin "2") (pinfunction "2_2") (pintype "passive"))
      (node (ref "C117") (pin "2") (pinfunction "2_2") (pintype "passive"))
      (node (ref "C118") (pin "2") (pinfunction "2_2") (pintype "passive"))
      (node (ref "C119") (pin "1") (pinfunction "1_1") (pintype "passive"))
      (node (ref "C121") (pin "2") (pinfunction "2_2") (pintype "passive"))
      (node (ref "C122") (pin "2") (pinfunction "2_2") (pintype "passive"))
      (node (ref "C123") (pin "2") (pinfunction "2_2") (pintype "passive"))
      (node (ref "C124") (pin "2") (pinfunction "2_2") (pintype "passive"))
      (node (ref "C125") (pin "2") (pinfunction "2_2") (pintype "passive"))
      (node (ref "C126") (pin "2") (pinfunction "2_2") (pintype "passive"))
      (node (ref "C130") (pin "2") (pinfunction "2_2") (pintype "passive"))
      (node (ref "C131") (pin "2") (pinfunction "2_2") (pintype "passive"))
      (node (ref "C132") (pin "2") (pinfunction "2_2") (pintype "passive"))
      (node (ref "C136") (pin "2") (pinfunction "2_2") (pintype "passive"))
      (node (ref "C137") (pin "2") (pinfunction "2_2") (pintype "passive"))
      (node (ref "C138") (pin "2") (pinfunction "2_2") (pintype "passive"))
      (node (ref "C139") (pin "2") (pinfunction "2_2") (pintype "passive"))
      (node (ref "C140") (pin "2") (pinfunction "2_2") (pintype "passive"))
      (node (ref "C141") (pin "1") (pinfunction "1_1") (pintype "passive"))
      (node (ref "C142") (pin "2") (pinfunction "2_2") (pintype "passive"))
      (node (ref "C143") (pin "1") (pinfunction "1_1") (pintype "passive"))
      (node (ref "C144") (pin "2") (pinfunction "2_2") (pintype "passive"))
      (node (ref "C145") (pin "1") (pinfunction "1_1") (pintype "passive"))
      (node (ref "C146") (pin "2") (pinfunction "2_2") (pintype "passive"))
      (node (ref "C81") (pin "2") (pinfunction "2_2") (pintype "passive"))
      (node (ref "C82") (pin "2") (pinfunction "2_2") (pintype "passive"))
      (node (ref "C83") (pin "1") (pinfunction "1_1") (pintype "passive"))
      (node (ref "C84") (pin "2") (pinfunction "2_2") (pintype "passive"))
      (node (ref "C85") (pin "1") (pinfunction "1_1") (pintype "passive"))
      (node (ref "C86") (pin "2") (pinfunction "2_2") (pintype "passive"))
      (node (ref "C87") (pin "1") (pinfunction "1_1") (pintype "passive"))
      (node (ref "C88") (pin "2") (pinfunction "2_2") (pintype "passive"))
      (node (ref "C89") (pin "2") (pinfunction "2_2") (pintype "passive"))
      (node (ref "C90") (pin "2") (pinfunction "2_2") (pintype "passive"))
      (node (ref "C94") (pin "2") (pinfunction "2_2") (pintype "passive"))
      (node (ref "C95") (pin "2") (pinfunction "2_2") (pintype "passive"))
      (node (ref "C96") (pin "2") (pinfunction "2_2") (pintype "passive"))
      (node (ref "DA1") (pin "17") (pinfunction "PAD_17") (pintype "passive"))
      (node (ref "IC10") (pin "10") (pinfunction "GND_10") (pintype "passive"))
      (node (ref "IC10") (pin "12") (pinfunction "GND_12") (pintype "passive"))
      (node (ref "IC10") (pin "14") (pinfunction "GND_14") (pintype "passive"))
      (node (ref "IC10") (pin "16") (pinfunction "GND_16") (pintype "passive"))
      (node (ref "IC10") (pin "17") (pinfunction "GND_17") (pintype "passive"))
      (node (ref "IC10") (pin "5") (pinfunction "GND_5") (pintype "passive"))
      (node (ref "IC10") (pin "7") (pinfunction "GND_7") (pintype "passive"))
      (node (ref "IC10") (pin "9") (pinfunction "GDN_9") (pintype "passive"))
      (node (ref "IC11") (pin "10") (pinfunction "GND_10") (pintype "passive"))
      (node (ref "IC11") (pin "12") (pinfunction "GND_12") (pintype "passive"))
      (node (ref "IC11") (pin "13") (pinfunction "GND_13") (pintype "passive"))
      (node (ref "IC11") (pin "14") (pinfunction "GND_14") (pintype "passive"))
      (node (ref "IC11") (pin "16") (pinfunction "GND_16") (pintype "passive"))
      (node (ref "IC11") (pin "17") (pinfunction "GND_17") (pintype "passive"))
      (node (ref "IC11") (pin "4") (pinfunction "V2_4") (pintype "power_in"))
      (node (ref "IC11") (pin "5") (pinfunction "GND_5") (pintype "passive"))
      (node (ref "IC11") (pin "7") (pinfunction "GND_7") (pintype "passive"))
      (node (ref "IC11") (pin "8") (pinfunction "GND_8") (pintype "passive"))
      (node (ref "IC11") (pin "9") (pinfunction "GDN_9") (pintype "passive"))
      (node (ref "IC12") (pin "10") (pinfunction "GND_10") (pintype "passive"))
      (node (ref "IC12") (pin "12") (pinfunction "GND_12") (pintype "passive"))
      (node (ref "IC12") (pin "14") (pinfunction "GND_14") (pintype "passive"))
      (node (ref "IC12") (pin "16") (pinfunction "GND_16") (pintype "passive"))
      (node (ref "IC12") (pin "17") (pinfunction "GND_17") (pintype "passive"))
      (node (ref "IC12") (pin "5") (pinfunction "GND_5") (pintype "passive"))
      (node (ref "IC12") (pin "7") (pinfunction "GND_7") (pintype "passive"))
      (node (ref "IC12") (pin "9") (pinfunction "GDN_9") (pintype "passive"))
      (node (ref "IC13") (pin "10") (pinfunction "GND_10") (pintype "passive"))
      (node (ref "IC13") (pin "12") (pinfunction "GND_12") (pintype "passive"))
      (node (ref "IC13") (pin "14") (pinfunction "GND_14") (pintype "passive"))
      (node (ref "IC13") (pin "16") (pinfunction "GND_16") (pintype "passive"))
      (node (ref "IC13") (pin "17") (pinfunction "GND_17") (pintype "passive"))
      (node (ref "IC13") (pin "5") (pinfunction "GND_5") (pintype "passive"))
      (node (ref "IC13") (pin "7") (pinfunction "GND_7") (pintype "passive"))
      (node (ref "IC13") (pin "9") (pinfunction "GDN_9") (pintype "passive"))
      (node (ref "IC8") (pin "10") (pinfunction "GND_10") (pintype "passive"))
      (node (ref "IC8") (pin "12") (pinfunction "GND_12") (pintype "passive"))
      (node (ref "IC8") (pin "13") (pinfunction "GND_13") (pintype "passive"))
      (node (ref "IC8") (pin "14") (pinfunction "GND_14") (pintype "passive"))
      (node (ref "IC8") (pin "16") (pinfunction "GND_16") (pintype "passive"))
      (node (ref "IC8") (pin "17") (pinfunction "GND_17") (pintype "passive"))
      (node (ref "IC8") (pin "4") (pinfunction "V2_4") (pintype "power_in"))
      (node (ref "IC8") (pin "5") (pinfunction "GND_5") (pintype "passive"))
      (node (ref "IC8") (pin "7") (pinfunction "GND_7") (pintype "passive"))
      (node (ref "IC8") (pin "8") (pinfunction "GND_8") (pintype "passive"))
      (node (ref "IC8") (pin "9") (pinfunction "GDN_9") (pintype "passive"))
      (node (ref "IC9") (pin "10") (pinfunction "GND_10") (pintype "passive"))
      (node (ref "IC9") (pin "12") (pinfunction "GND_12") (pintype "passive"))
      (node (ref "IC9") (pin "14") (pinfunction "GND_14") (pintype "passive"))
      (node (ref "IC9") (pin "16") (pinfunction "GND_16") (pintype "passive"))
      (node (ref "IC9") (pin "17") (pinfunction "GND_17") (pintype "passive"))
      (node (ref "IC9") (pin "5") (pinfunction "GND_5") (pintype "passive"))
      (node (ref "IC9") (pin "7") (pinfunction "GND_7") (pintype "passive"))
      (node (ref "IC9") (pin "9") (pinfunction "GDN_9") (pintype "passive"))
      (node (ref "L20") (pin "1") (pinfunction "1_1") (pintype "passive"))
      (node (ref "L21") (pin "1") (pinfunction "1_1") (pintype "passive"))
      (node (ref "L22") (pin "1") (pinfunction "1_1") (pintype "passive"))
      (node (ref "L27") (pin "1") (pinfunction "1_1") (pintype "passive"))
      (node (ref "L28") (pin "1") (pinfunction "1_1") (pintype "passive"))
      (node (ref "L29") (pin "1") (pinfunction "1_1") (pintype "passive"))
    )
    (net (code "21") (name "Net-(C81-Pad1)") (class "Default")
      (node (ref "C81") (pin "1") (pinfunction "1_1") (pintype "passive"))
      (node (ref "L10") (pin "2") (pinfunction "2_2") (pintype "passive"))
      (node (ref "R82") (pin "1") (pinfunction "1_1") (pintype "passive"))
    )
    (net (code "22") (name "Net-(C91-Pad2)") (class "Default")
      (node (ref "C91") (pin "2") (pinfunction "2_2") (pintype "passive"))
      (node (ref "C94") (pin "1") (pinfunction "1_1") (pintype "passive"))
      (node (ref "C97") (pin "1") (pinfunction "1_1") (pintype "passive"))
      (node (ref "L11") (pin "2") (pinfunction "2_2") (pintype "passive"))
      (node (ref "L14") (pin "1") (pinfunction "1_1") (pintype "passive"))
    )
    (net (code "23") (name "Net-(C92-Pad2)") (class "Default")
      (node (ref "C92") (pin "2") (pinfunction "2_2") (pintype "passive"))
      (node (ref "C95") (pin "1") (pinfunction "1_1") (pintype "passive"))
      (node (ref "C98") (pin "1") (pinfunction "1_1") (pintype "passive"))
      (node (ref "L12") (pin "2") (pinfunction "2_2") (pintype "passive"))
      (node (ref "L15") (pin "1") (pinfunction "1_1") (pintype "passive"))
    )
    (net (code "24") (name "Net-(C93-Pad2)") (class "Default")
      (node (ref "C93") (pin "2") (pinfunction "2_2") (pintype "passive"))
      (node (ref "C96") (pin "1") (pinfunction "1_1") (pintype "passive"))
      (node (ref "C99") (pin "1") (pinfunction "1_1") (pintype "passive"))
      (node (ref "L13") (pin "2") (pinfunction "2_2") (pintype "passive"))
      (node (ref "L16") (pin "1") (pinfunction "1_1") (pintype "passive"))
    )
    (net (code "25") (name "Net-(C100-Pad1)") (class "Default")
      (node (ref "C100") (pin "1") (pinfunction "1_1") (pintype "passive"))
      (node (ref "L17") (pin "2") (pinfunction "2_2") (pintype "passive"))
      (node (ref "R83") (pin "1") (pinfunction "1_1") (pintype "passive"))
    )
    (net (code "26") (name "Net-(C104-Pad1)") (class "Default")
      (node (ref "C104") (pin "1") (pinfunction "1_1") (pintype "passive"))
      (node (ref "L18") (pin "2") (pinfunction "2_2") (pintype "passive"))
      (node (ref "R87") (pin "1") (pinfunction "1_1") (pintype "passive"))
    )
    (net (code "27") (name "Net-(C105-Pad2)") (class "Default")
      (node (ref "C105") (pin "2") (pinfunction "2_2") (pintype "passive"))
      (node (ref "R84") (pin "1") (pinfunction "1_1") (pintype "passive"))
      (node (ref "R85") (pin "1") (pinfunction "1_1") (pintype "passive"))
      (node (ref "R86") (pin "1") (pinfunction "1_1") (pintype "passive"))
    )
    (net (code "28") (name "Net-(C106-Pad2)") (class "Default")
      (node (ref "C106") (pin "2") (pinfunction "2_2") (pintype "passive"))
      (node (ref "DA1") (pin "2") (pinfunction "RFIN_2") (pintype "passive"))
      (node (ref "DA1") (pin "3") (pinfunction "RFIN_3") (pintype "passive"))
      (node (ref "L23") (pin "1") (pinfunction "1_1") (pintype "passive"))
    )
    (net (code "29") (name "Net-(C110-Pad2)") (class "Default")
      (node (ref "C110") (pin "2") (pinfunction "2_2") (pintype "passive"))
      (node (ref "L23") (pin "2") (pinfunction "2_2") (pintype "passive"))
      (node (ref "R86") (pin "2") (pinfunction "2_2") (pintype "passive"))
    )
    (net (code "30") (name "Net-(C111-Pad1)") (class "Default")
      (node (ref "C111") (pin "1") (pinfunction "1_1") (pintype "passive"))
      (node (ref "L19") (pin "2") (pinfunction "2_2") (pintype "passive"))
      (node (ref "R88") (pin "1") (pinfunction "1_1") (pintype "passive"))
    )
    (net (code "31") (name "Net-(C112-Pad1)") (class "Default")
      (node (ref "C112") (pin "1") (pinfunction "1_1") (pintype "passive"))
      (node (ref "L24") (pin "2") (pinfunction "2_2") (pintype "passive"))
    )
    (net (code "32") (name "Net-(C113-Pad1)") (class "Default")
      (node (ref "C113") (pin "1") (pinfunction "1_1") (pintype "passive"))
      (node (ref "L25") (pin "2") (pinfunction "2_2") (pintype "passive"))
    )
    (net (code "33") (name "Net-(C114-Pad1)") (class "Default")
      (node (ref "C114") (pin "1") (pinfunction "1_1") (pintype "passive"))
      (node (ref "L26") (pin "2") (pinfunction "2_2") (pintype "passive"))
    )
    (net (code "34") (name "Net-(C115-Pad1)") (class "Default")
      (node (ref "C115") (pin "1") (pinfunction "1_1") (pintype "passive"))
      (node (ref "L31") (pin "2") (pinfunction "2_2") (pintype "passive"))
      (node (ref "R89") (pin "1") (pinfunction "1_1") (pintype "passive"))
    )
    (net (code "35") (name "Net-(C119-Pad2)") (class "Default")
      (node (ref "C119") (pin "2") (pinfunction "2_2") (pintype "passive"))
      (node (ref "FB16") (pin "1") (pinfunction "1_1") (pintype "passive"))
      (node (ref "L30") (pin "2") (pinfunction "2_2") (pintype "passive"))
    )
    (net (code "36") (name "Net-(C120-Pad1)") (class "Default")
      (node (ref "C120") (pin "1") (pinfunction "1_1") (pintype "passive"))
      (node (ref "DA1") (pin "10") (pinfunction "RFOUT_10") (pintype "passive"))
      (node (ref "DA1") (pin "11") (pinfunction "RFOUT_11") (pintype "passive"))
      (node (ref "L30") (pin "1") (pinfunction "1_1") (pintype "passive"))
    )
    (net (code "37") (name "Net-(C121-Pad1)") (class "Default")
      (node (ref "C121") (pin "1") (pinfunction "1_1") (pintype "passive"))
      (node (ref "L32") (pin "2") (pinfunction "2_2") (pintype "passive"))
      (node (ref "R90") (pin "1") (pinfunction "1_1") (pintype "passive"))
    )
    (net (code "38") (name "Net-(C122-Pad1)") (class "Default")
      (node (ref "C122") (pin "1") (pinfunction "1_1") (pintype "passive"))
      (node (ref "L33") (pin "2") (pinfunction "2_2") (pintype "passive"))
      (node (ref "R91") (pin "1") (pinfunction "1_1") (pintype "passive"))
    )
    (net (code "39") (name "Net-(C126-Pad1)") (class "Default")
      (node (ref "C126") (pin "1") (pinfunction "1_1") (pintype "passive"))
      (node (ref "L37") (pin "2") (pinfunction "2_2") (pintype "passive"))
      (node (ref "R92") (pin "1") (pinfunction "1_1") (pintype "passive"))
    )
    (net (code "40") (name "Net-(C127-Pad2)") (class "Default")
      (node (ref "C127") (pin "2") (pinfunction "2_2") (pintype "passive"))
      (node (ref "C130") (pin "1") (pinfunction "1_1") (pintype "passive"))
      (node (ref "C133") (pin "1") (pinfunction "1_1") (pintype "passive"))
      (node (ref "L34") (pin "2") (pinfunction "2_2") (pintype "passive"))
      (node (ref "L38") (pin "1") (pinfunction "1_1") (pintype "passive"))
    )
    (net (code "41") (name "Net-(C128-Pad2)") (class "Default")
      (node (ref "C128") (pin "2") (pinfunction "2_2") (pintype "passive"))
      (node (ref "C131") (pin "1") (pinfunction "1_1") (pintype "passive"))
      (node (ref "C134") (pin "1") (pinfunction "1_1") (pintype "passive"))
      (node (ref "L35") (pin "2") (pinfunction "2_2") (pintype "passive"))
      (node (ref "L39") (pin "1") (pinfunction "1_1") (pintype "passive"))
    )
    (net (code "42") (name "Net-(C129-Pad2)") (class "Default")
      (node (ref "C129") (pin "2") (pinfunction "2_2") (pintype "passive"))
      (node (ref "C132") (pin "1") (pinfunction "1_1") (pintype "passive"))
      (node (ref "C135") (pin "1") (pinfunction "1_1") (pintype "passive"))
      (node (ref "L36") (pin "2") (pinfunction "2_2") (pintype "passive"))
      (node (ref "L40") (pin "1") (pinfunction "1_1") (pintype "passive"))
    )
    (net (code "43") (name "Net-(C139-Pad1)") (class "Default")
      (node (ref "C139") (pin "1") (pinfunction "1_1") (pintype "passive"))
      (node (ref "L44") (pin "2") (pinfunction "2_2") (pintype "passive"))
      (node (ref "R93") (pin "1") (pinfunction "1_1") (pintype "passive"))
    )
    (net (code "44") (name "Net-(C146-Pad1)") (class "Default")
      (node (ref "C146") (pin "1") (pinfunction "1_1") (pintype "passive"))
      (node (ref "L45") (pin "2") (pinfunction "2_2") (pintype "passive"))
      (node (ref "R94") (pin "1") (pinfunction "1_1") (pintype "passive"))
    )
    (net (code "45") (name "Net-(IC8A-RF1)") (class "Default")
      (node (ref "C90") (pin "1") (pinfunction "1_1") (pintype "passive"))
      (node (ref "C93") (pin "1") (pinfunction "1_1") (pintype "passive"))
      (node (ref "IC8") (pin "15") (pinfunction "RF1_15") (pintype "passive"))
      (node (ref "L13") (pin "1") (pinfunction "1_1") (pintype "passive"))
    )
    (net (code "46") (name "Net-(IC8A-RF2)") (class "Default")
      (node (ref "C89") (pin "1") (pinfunction "1_1") (pintype "passive"))
      (node (ref "C92") (pin "1") (pinfunction "1_1") (pintype "passive"))
      (node (ref "IC8") (pin "6") (pinfunction "RF2_6") (pintype "passive"))
      (node (ref "L12") (pin "1") (pinfunction "1_1") (pintype "passive"))
    )
    (net (code "47") (name "Net-(IC8A-V1)") (class "Default")
      (node (ref "IC8") (pin "3") (pinfunction "V1_3") (pintype "passive"))
      (node (ref "R82") (pin "2") (pinfunction "2_2") (pintype "passive"))
    )
    (net (code "48") (name "Net-(IC8B-VCP)") (class "Default")
      (node (ref "C82") (pin "1") (pinfunction "1_1") (pintype "passive"))
      (node (ref "IC8") (pin "1") (pinfunction "VCP_1") (pintype "passive"))
    )
    (net (code "49") (name "Net-(IC8B-VDD)") (class "Default")
      (node (ref "C83") (pin "2") (pinfunction "2_2") (pintype "passive"))
      (node (ref "IC8") (pin "2") (pinfunction "VDD_2") (pintype "passive"))
      (node (ref "L7") (pin "2") (pinfunction "2_2") (pintype "passive"))
    )
    (net (code "50") (name "Net-(IC9A-ANT)") (class "Default")
      (node (ref "C106") (pin "1") (pinfunction "1_1") (pintype "passive"))
      (node (ref "IC9") (pin "11") (pinfunction "ANT_11") (pintype "passive"))
    )
    (net (code "51") (name "Net-(IC9A-RF1)") (class "Default")
      (node (ref "C101") (pin "1") (pinfunction "1_1") (pintype "passive"))
      (node (ref "C97") (pin "2") (pinfunction "2_2") (pintype "passive"))
      (node (ref "IC9") (pin "13") (pinfunction "RF1_13") (pintype "passive"))
      (node (ref "L14") (pin "2") (pinfunction "2_2") (pintype "passive"))
    )
    (net (code "52") (name "Net-(IC9A-RF3)") (class "Default")
      (node (ref "C103") (pin "1") (pinfunction "1_1") (pintype "passive"))
      (node (ref "C99") (pin "2") (pinfunction "2_2") (pintype "passive"))
      (node (ref "IC9") (pin "8") (pinfunction "RF3_8") (pintype "passive"))
      (node (ref "L16") (pin "2") (pinfunction "2_2") (pintype "passive"))
    )
    (net (code "53") (name "Net-(IC9A-RF4)") (class "Default")
      (node (ref "C102") (pin "1") (pinfunction "1_1") (pintype "passive"))
      (node (ref "C98") (pin "2") (pinfunction "2_2") (pintype "passive"))
      (node (ref "IC9") (pin "6") (pinfunction "RF4_6") (pintype "passive"))
      (node (ref "L15") (pin "2") (pinfunction "2_2") (pintype "passive"))
    )
    (net (code "54") (name "Net-(IC9A-V1)") (class "Default")
      (node (ref "IC9") (pin "3") (pinfunction "V1_3") (pintype "passive"))
      (node (ref "R88") (pin "2") (pinfunction "2_2") (pintype "passive"))
    )
    (net (code "55") (name "Net-(IC9A-V2)") (class "Default")
      (node (ref "IC9") (pin "4") (pinfunction "V2_4") (pintype "power_in"))
      (node (ref "R87") (pin "2") (pinfunction "2_2") (pintype "passive"))
    )
    (net (code "56") (name "Net-(IC9B-VCP)") (class "Default")
      (node (ref "C84") (pin "1") (pinfunction "1_1") (pintype "passive"))
      (node (ref "IC9") (pin "1") (pinfunction "VCP_1") (pintype "passive"))
    )
    (net (code "57") (name "Net-(IC9B-VDD)") (class "Default")
      (node (ref "C85") (pin "2") (pinfunction "2_2") (pintype "passive"))
      (node (ref "IC9") (pin "2") (pinfunction "VDD_2") (pintype "passive"))
      (node (ref "L8") (pin "2") (pinfunction "2_2") (pintype "passive"))
    )
    (net (code "58") (name "Net-(IC10A-ANT)") (class "Default")
      (node (ref "IC10") (pin "11") (pinfunction "ANT_11") (pintype "passive"))
      (node (ref "IC13") (pin "15") (pinfunction "RF2_15") (pintype "passive"))
    )
    (net (code "59") (name "Net-(IC10A-RF1)") (class "Default")
      (node (ref "C114") (pin "2") (pinfunction "2_2") (pintype "passive"))
      (node (ref "C118") (pin "1") (pinfunction "1_1") (pintype "passive"))
      (node (ref "IC10") (pin "13") (pinfunction "RF1_13") (pintype "passive"))
      (node (ref "L29") (pin "2") (pinfunction "2_2") (pintype "passive"))
    )
    (net (code "60") (name "Net-(IC10A-RF2)") (class "Default")
      (node (ref "C113") (pin "2") (pinfunction "2_2") (pintype "passive"))
      (node (ref "C117") (pin "1") (pinfunction "1_1") (pintype "passive"))
      (node (ref "IC10") (pin "15") (pinfunction "RF2_15") (pintype "passive"))
      (node (ref "L28") (pin "2") (pinfunction "2_2") (pintype "passive"))
    )
    (net (code "61") (name "Net-(IC10A-RF4)") (class "Default")
      (node (ref "C112") (pin "2") (pinfunction "2_2") (pintype "passive"))
      (node (ref "C116") (pin "1") (pinfunction "1_1") (pintype "passive"))
      (node (ref "IC10") (pin "6") (pinfunction "RF4_6") (pintype "passive"))
      (node (ref "L27") (pin "2") (pinfunction "2_2") (pintype "passive"))
    )
    (net (code "62") (name "Net-(IC10A-V1)") (class "Default")
      (node (ref "IC10") (pin "3") (pinfunction "V1_3") (pintype "passive"))
      (node (ref "R92") (pin "2") (pinfunction "2_2") (pintype "passive"))
    )
    (net (code "63") (name "Net-(IC10A-V2)") (class "Default")
      (node (ref "IC10") (pin "4") (pinfunction "V2_4") (pintype "power_in"))
      (node (ref "R91") (pin "2") (pinfunction "2_2") (pintype "passive"))
    )
    (net (code "64") (name "Net-(IC10B-VCP)") (class "Default")
      (node (ref "C86") (pin "1") (pinfunction "1_1") (pintype "passive"))
      (node (ref "IC10") (pin "1") (pinfunction "VCP_1") (pintype "passive"))
    )
    (net (code "65") (name "Net-(IC10B-VDD)") (class "Default")
      (node (ref "C87") (pin "2") (pinfunction "2_2") (pintype "passive"))
      (node (ref "IC10") (pin "2") (pinfunction "VDD_2") (pintype "passive"))
      (node (ref "L9") (pin "2") (pinfunction "2_2") (pintype "passive"))
    )
    (net (code "66") (name "Net-(IC11A-RF1)") (class "Default")
      (node (ref "C108") (pin "1") (pinfunction "1_1") (pintype "passive"))
      (node (ref "IC11") (pin "15") (pinfunction "RF1_15") (pintype "passive"))
      (node (ref "L21") (pin "2") (pinfunction "2_2") (pintype "passive"))
      (node (ref "L25") (pin "1") (pinfunction "1_1") (pintype "passive"))
    )
    (net (code "67") (name "Net-(IC11A-RF2)") (class "Default")
      (node (ref "C109") (pin "1") (pinfunction "1_1") (pintype "passive"))
      (node (ref "IC11") (pin "6") (pinfunction "RF2_6") (pintype "passive"))
      (node (ref "L22") (pin "2") (pinfunction "2_2") (pintype "passive"))
      (node (ref "L26") (pin "1") (pinfunction "1_1") (pintype "passive"))
    )
    (net (code "68") (name "Net-(IC11A-V1)") (class "Default")
      (node (ref "IC11") (pin "3") (pinfunction "V1_3") (pintype "passive"))
      (node (ref "R83") (pin "2") (pinfunction "2_2") (pintype "passive"))
    )
    (net (code "69") (name "Net-(IC11B-VCP)") (class "Default")
      (node (ref "C140") (pin "1") (pinfunction "1_1") (pintype "passive"))
      (node (ref "IC11") (pin "1") (pinfunction "VCP_1") (pintype "passive"))
    )
    (net (code "70") (name "Net-(IC11B-VDD)") (class "Default")
      (node (ref "C141") (pin "2") (pinfunction "2_2") (pintype "passive"))
      (node (ref "IC11") (pin "2") (pinfunction "VDD_2") (pintype "passive"))
      (node (ref "L41") (pin "2") (pinfunction "2_2") (pintype "passive"))
    )
    (net (code "71") (name "Net-(IC12A-ANT)") (class "Default")
      (node (ref "C120") (pin "2") (pinfunction "2_2") (pintype "passive"))
      (node (ref "IC12") (pin "11") (pinfunction "ANT_11") (pintype "passive"))
    )
    (net (code "72") (name "Net-(IC12A-RF1)") (class "Default")
      (node (ref "C125") (pin "1") (pinfunction "1_1") (pintype "passive"))
      (node (ref "C129") (pin "1") (pinfunction "1_1") (pintype "passive"))
      (node (ref "IC12") (pin "13") (pinfunction "RF1_13") (pintype "passive"))
      (node (ref "L36") (pin "1") (pinfunction "1_1") (pintype "passive"))
    )
    (net (code "73") (name "Net-(IC12A-RF3)") (class "Default")
      (node (ref "C124") (pin "1") (pinfunction "1_1") (pintype "passive"))
      (node (ref "C128") (pin "1") (pinfunction "1_1") (pintype "passive"))
      (node (ref "IC12") (pin "8") (pinfunction "RF3_8") (pintype "passive"))
      (node (ref "L35") (pin "1") (pinfunction "1_1") (pintype "passive"))
    )
    (net (code "74") (name "Net-(IC12A-RF4)") (class "Default")
      (node (ref "C123") (pin "1") (pinfunction "1_1") (pintype "passive"))
      (node (ref "C127") (pin "1") (pinfunction "1_1") (pintype "passive"))
      (node (ref "IC12") (pin "6") (pinfunction "RF4_6") (pintype "passive"))
      (node (ref "L34") (pin "1") (pinfunction "1_1") (pintype "passive"))
    )
    (net (code "75") (name "Net-(IC12A-V1)") (class "Default")
      (node (ref "IC12") (pin "3") (pinfunction "V1_3") (pintype "passive"))
      (node (ref "R89") (pin "2") (pinfunction "2_2") (pintype "passive"))
    )
    (net (code "76") (name "Net-(IC12A-V2)") (class "Default")
      (node (ref "IC12") (pin "4") (pinfunction "V2_4") (pintype "power_in"))
      (node (ref "R90") (pin "2") (pinfunction "2_2") (pintype "passive"))
    )
    (net (code "77") (name "Net-(IC12B-VCP)") (class "Default")
      (node (ref "C142") (pin "1") (pinfunction "1_1") (pintype "passive"))
      (node (ref "IC12") (pin "1") (pinfunction "VCP_1") (pintype "passive"))
    )
    (net (code "78") (name "Net-(IC12B-VDD)") (class "Default")
      (node (ref "C143") (pin "2") (pinfunction "2_2") (pintype "passive"))
      (node (ref "IC12") (pin "2") (pinfunction "VDD_2") (pintype "passive"))
      (node (ref "L42") (pin "2") (pinfunction "2_2") (pintype "passive"))
    )
    (net (code "79") (name "Net-(IC13A-RF1)") (class "Default")
      (node (ref "C133") (pin "2") (pinfunction "2_2") (pintype "passive"))
      (node (ref "C136") (pin "1") (pinfunction "1_1") (pintype "passive"))
      (node (ref "IC13") (pin "13") (pinfunction "RF1_13") (pintype "passive"))
      (node (ref "L38") (pin "2") (pinfunction "2_2") (pintype "passive"))
    )
    (net (code "80") (name "Net-(IC13A-RF3)") (class "Default")
      (node (ref "C134") (pin "2") (pinfunction "2_2") (pintype "passive"))
      (node (ref "C137") (pin "1") (pinfunction "1_1") (pintype "passive"))
      (node (ref "IC13") (pin "8") (pinfunction "RF3_8") (pintype "passive"))
      (node (ref "L39") (pin "2") (pinfunction "2_2") (pintype "passive"))
    )
    (net (code "81") (name "Net-(IC13A-RF4)") (class "Default")
      (node (ref "C135") (pin "2") (pinfunction "2_2") (pintype "passive"))
      (node (ref "C138") (pin "1") (pinfunction "1_1") (pintype "passive"))
      (node (ref "IC13") (pin "6") (pinfunction "RF4_6") (pintype "passive"))
      (node (ref "L40") (pin "2") (pinfunction "2_2") (pintype "passive"))
    )
    (net (code "82") (name "Net-(IC13A-V1)") (class "Default")
      (node (ref "IC13") (pin "3") (pinfunction "V1_3") (pintype "passive"))
      (node (ref "R94") (pin "2") (pinfunction "2_2") (pintype "passive"))
    )
    (net (code "83") (name "Net-(IC13A-V2)") (class "Default")
      (node (ref "IC13") (pin "4") (pinfunction "V2_4") (pintype "power_in"))
      (node (ref "R93") (pin "2") (pinfunction "2_2") (pintype "passive"))
    )
    (net (code "84") (name "Net-(IC13B-VCP)") (class "Default")
      (node (ref "C144") (pin "1") (pinfunction "1_1") (pintype "passive"))
      (node (ref "IC13") (pin "1") (pinfunction "VCP_1") (pintype "passive"))
    )
    (net (code "85") (name "Net-(IC13B-VDD)") (class "Default")
      (node (ref "C145") (pin "2") (pinfunction "2_2") (pintype "passive"))
      (node (ref "IC13") (pin "2") (pinfunction "VDD_2") (pintype "passive"))
      (node (ref "L43") (pin "2") (pinfunction "2_2") (pintype "passive"))
    )
    (net (code "86") (name "unconnected-(IC9A-RF2-Pad15)") (class "Default")
      (node (ref "IC9") (pin "15") (pinfunction "RF2_15") (pintype "passive"))
    )
    (net (code "87") (name "unconnected-(IC10A-RF3-Pad8)") (class "Default")
      (node (ref "IC10") (pin "8") (pinfunction "RF3_8") (pintype "passive"))
    )
    (net (code "88") (name "unconnected-(IC12A-RF2-Pad15)") (class "Default")
      (node (ref "IC12") (pin "15") (pinfunction "RF2_15") (pintype "passive"))
    )
  )
)
